# detcord-mdrv.net
KiCad netlist of a schematic drawn in EAGLE
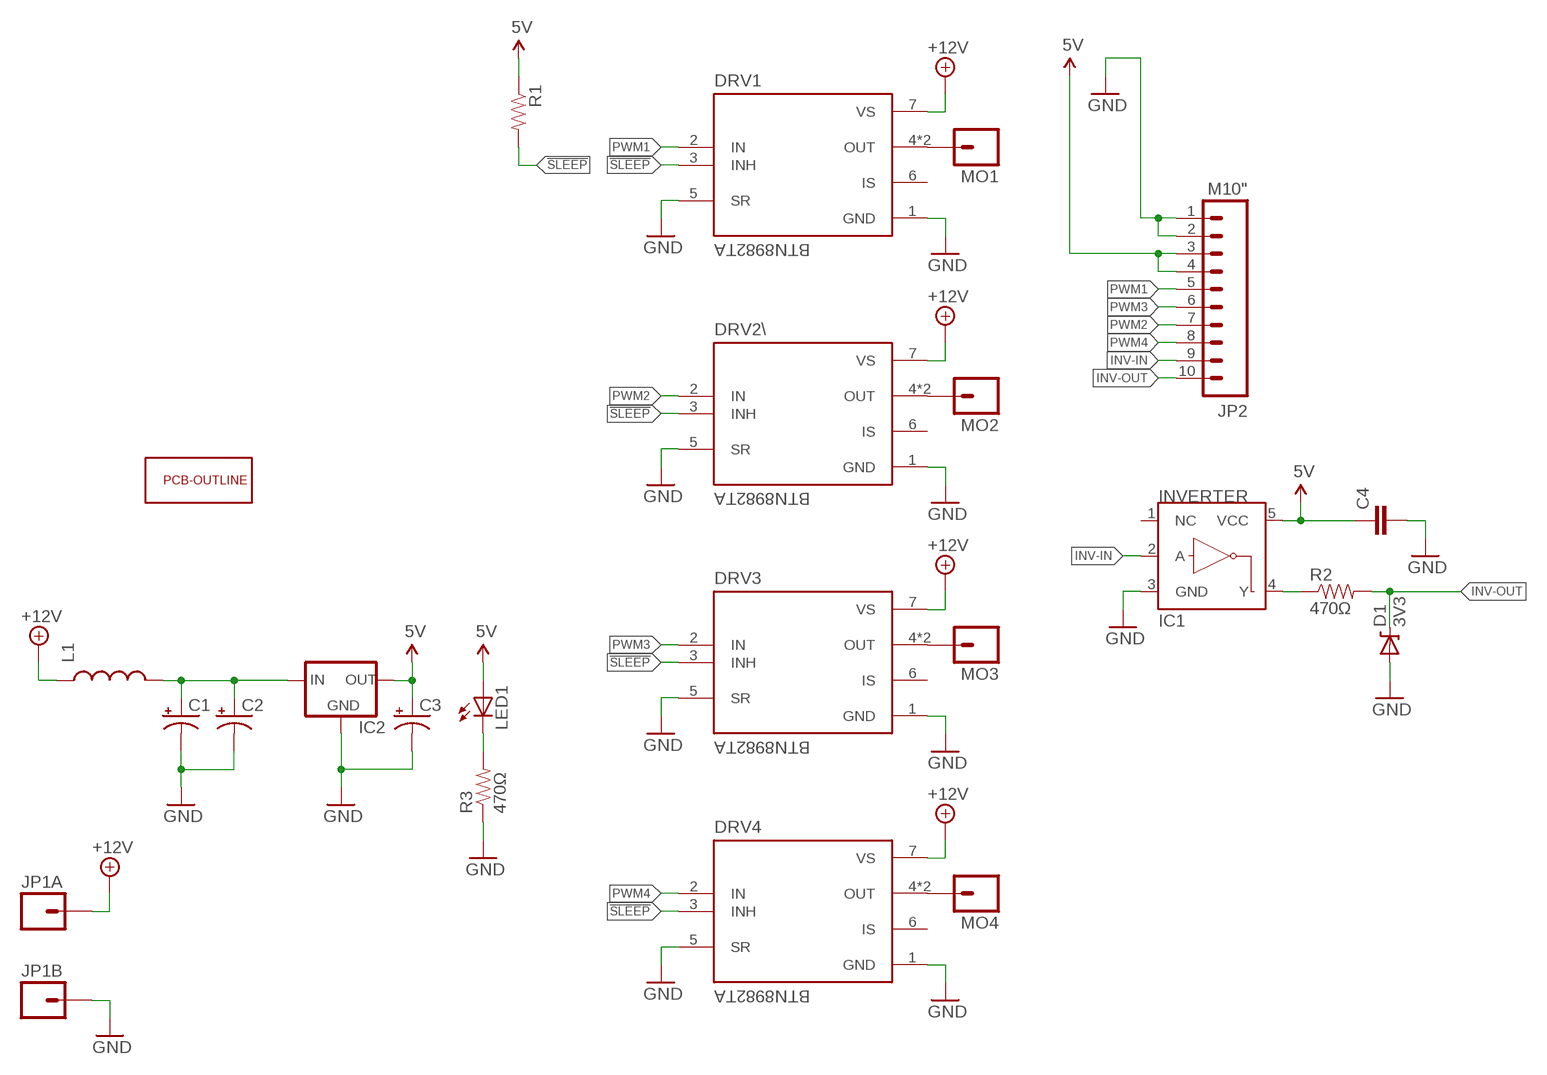
[diagram p0: schematic, sheet 1]

(export (version "E")
  (design (tool "Eeschema 10.0.6"))
  (components
    (comp (ref "C1")
      (value "CAP_POLD")
      (footprint "eagle-import:PANASONIC_D")
      (libsource (lib "eagle-import") (part "CAP_POLD"))
    )
    (comp (ref "C2")
      (value "CAP_POLD")
      (footprint "eagle-import:PANASONIC_D")
      (libsource (lib "eagle-import") (part "CAP_POLD"))
    )
    (comp (ref "C3")
      (value "CAP_POLD")
      (footprint "eagle-import:PANASONIC_D")
      (libsource (lib "eagle-import") (part "CAP_POLD"))
    )
    (comp (ref "C4")
      (value "CAP0603-CAP")
      (footprint "eagle-import:0603-CAP")
      (libsource (lib "eagle-import") (part "CAP0603-CAP"))
    )
    (comp (ref "D1")
      (value "3V3")
      (footprint "eagle-import:SOD-323")
      (libsource (lib "eagle-import") (part "DIODE-ZENER-BZT52"))
    )
    (comp (ref "DRV1")
      (value "BTN8982TA")
      (footprint "eagle-import:DPAK127P1500X440-8N")
      (fields (field (name "MF") "Infineon Technologies"))
      (libsource (lib "eagle-import") (part "BTN8982TA"))
    )
    (comp (ref "DRV2\\")
      (value "BTN8982TA")
      (footprint "eagle-import:DPAK127P1500X440-8N")
      (fields (field (name "MF") "Infineon Technologies"))
      (libsource (lib "eagle-import") (part "BTN8982TA"))
    )
    (comp (ref "DRV3")
      (value "BTN8982TA")
      (footprint "eagle-import:DPAK127P1500X440-8N")
      (fields (field (name "MF") "Infineon Technologies"))
      (libsource (lib "eagle-import") (part "BTN8982TA"))
    )
    (comp (ref "DRV4")
      (value "BTN8982TA")
      (footprint "eagle-import:DPAK127P1500X440-8N")
      (fields (field (name "MF") "Infineon Technologies"))
      (libsource (lib "eagle-import") (part "BTN8982TA"))
    )
    (comp (ref "IC1")
      (value "INVERTER")
      (footprint "eagle-import:SC70")
      (libsource (lib "eagle-import") (part "INVERTER{dblquote}{dblquote}"))
    )
    (comp (ref "IC2")
      (value "V_REG_78XXSINK")
      (footprint "eagle-import:TO220-IGO")
      (libsource (lib "eagle-import") (part "V_REG_78XXSINK"))
    )
    (comp (ref "JP1A")
      (value "M01PTH_2MM")
      (footprint "eagle-import:1X01_2MM")
      (libsource (lib "eagle-import") (part "M01PTH_2MM"))
    )
    (comp (ref "JP1B")
      (value "M01PTH_2MM")
      (footprint "eagle-import:1X01_2MM")
      (libsource (lib "eagle-import") (part "M01PTH_2MM"))
    )
    (comp (ref "JP2")
      (value "M10\"")
      (footprint "eagle-import:1X10")
      (libsource (lib "eagle-import") (part "M10{dblquote}"))
    )
    (comp (ref "L1")
      (value "INDUCTORCR54")
      (footprint "eagle-import:CR54")
      (libsource (lib "eagle-import") (part "INDUCTORCR54"))
    )
    (comp (ref "LED1")
      (value "LED0603")
      (footprint "eagle-import:LED-0603")
      (libsource (lib "eagle-import") (part "LED0603"))
    )
    (comp (ref "MO1")
      (value "M01PTH_2MM")
      (footprint "eagle-import:1X01_2MM")
      (libsource (lib "eagle-import") (part "M01PTH_2MM"))
    )
    (comp (ref "MO2")
      (value "M01PTH_2MM")
      (footprint "eagle-import:1X01_2MM")
      (libsource (lib "eagle-import") (part "M01PTH_2MM"))
    )
    (comp (ref "MO3")
      (value "M01PTH_2MM")
      (footprint "eagle-import:1X01_2MM")
      (libsource (lib "eagle-import") (part "M01PTH_2MM"))
    )
    (comp (ref "MO4")
      (value "M01PTH_2MM")
      (footprint "eagle-import:1X01_2MM")
      (libsource (lib "eagle-import") (part "M01PTH_2MM"))
    )
    (comp (ref "PCBOUTLINE1")
      (value "PCB-OUTLINE-38X24MM")
      (footprint "eagle-import:PCB-OUTLINE-38X24MM")
      (libsource (lib "eagle-import") (part "PCB-OUTLINE-38X24MM"))
    )
    (comp (ref "R1")
      (value "RESISTOR0603-RES")
      (footprint "eagle-import:0603-RES")
      (libsource (lib "eagle-import") (part "RESISTOR0603-RES"))
    )
    (comp (ref "R2")
      (value "470Ω")
      (footprint "eagle-import:0603-RES")
      (libsource (lib "eagle-import") (part "RESISTOR0603-RES"))
    )
    (comp (ref "R3")
      (value "470Ω")
      (footprint "eagle-import:0603-RES")
      (libsource (lib "eagle-import") (part "RESISTOR0603-RES"))
    )
  )
  (nets
    (net (code "1") (name "+12V") (class "Default")
      (node (ref "DRV1") (pin "7") (pinfunction "VS_7") (pintype "power_in"))
      (node (ref "DRV2\\") (pin "7") (pinfunction "VS_7") (pintype "power_in"))
      (node (ref "DRV3") (pin "7") (pinfunction "VS_7") (pintype "power_in"))
      (node (ref "DRV4") (pin "7") (pinfunction "VS_7") (pintype "power_in"))
      (node (ref "JP1A") (pin "1") (pinfunction "1_1") (pintype "passive"))
      (node (ref "L1") (pin "P$1") (pinfunction "1_P$1") (pintype "passive"))
    )
    (net (code "2") (name "/~{SLEEP}") (class "Default")
      (node (ref "DRV1") (pin "3") (pinfunction "INH_3") (pintype "input"))
      (node (ref "DRV2\\") (pin "3") (pinfunction "INH_3") (pintype "input"))
      (node (ref "DRV3") (pin "3") (pinfunction "INH_3") (pintype "input"))
      (node (ref "DRV4") (pin "3") (pinfunction "INH_3") (pintype "input"))
      (node (ref "R1") (pin "2") (pinfunction "2_2") (pintype "passive"))
    )
    (net (code "3") (name "5V") (class "Default")
      (node (ref "C3") (pin "+") (pinfunction "+_+") (pintype "passive"))
      (node (ref "C4") (pin "1") (pinfunction "1_1") (pintype "passive"))
      (node (ref "IC1") (pin "5") (pinfunction "VCC_5") (pintype "bidirectional"))
      (node (ref "IC2") (pin "OUT") (pinfunction "OUT_OUT") (pintype "output"))
      (node (ref "JP2") (pin "3") (pinfunction "3_3") (pintype "passive"))
      (node (ref "JP2") (pin "4") (pinfunction "4_4") (pintype "passive"))
      (node (ref "LED1") (pin "A") (pinfunction "A_A") (pintype "passive"))
      (node (ref "R1") (pin "1") (pinfunction "1_1") (pintype "passive"))
    )
    (net (code "4") (name "GND") (class "Default")
      (node (ref "C1") (pin "-") (pinfunction "-_-") (pintype "passive"))
      (node (ref "C2") (pin "-") (pinfunction "-_-") (pintype "passive"))
      (node (ref "C3") (pin "-") (pinfunction "-_-") (pintype "passive"))
      (node (ref "C4") (pin "2") (pinfunction "2_2") (pintype "passive"))
      (node (ref "D1") (pin "2") (pinfunction "A_2") (pintype "passive"))
      (node (ref "DRV1") (pin "1") (pinfunction "GND_1") (pintype "power_in"))
      (node (ref "DRV1") (pin "5") (pinfunction "SR_5") (pintype "input"))
      (node (ref "DRV2\\") (pin "1") (pinfunction "GND_1") (pintype "power_in"))
      (node (ref "DRV2\\") (pin "5") (pinfunction "SR_5") (pintype "input"))
      (node (ref "DRV3") (pin "1") (pinfunction "GND_1") (pintype "power_in"))
      (node (ref "DRV3") (pin "5") (pinfunction "SR_5") (pintype "input"))
      (node (ref "DRV4") (pin "1") (pinfunction "GND_1") (pintype "power_in"))
      (node (ref "DRV4") (pin "5") (pinfunction "SR_5") (pintype "input"))
      (node (ref "IC1") (pin "3") (pinfunction "GND_3") (pintype "bidirectional"))
      (node (ref "IC2") (pin "GND") (pinfunction "GND_GND") (pintype "input"))
      (node (ref "JP1B") (pin "1") (pinfunction "1_1") (pintype "passive"))
      (node (ref "JP2") (pin "1") (pinfunction "1_1") (pintype "passive"))
      (node (ref "JP2") (pin "2") (pinfunction "2_2") (pintype "passive"))
      (node (ref "R3") (pin "1") (pinfunction "1_1") (pintype "passive"))
    )
    (net (code "5") (name "INV-IN") (class "Default")
      (node (ref "IC1") (pin "2") (pinfunction "A_2") (pintype "bidirectional"))
      (node (ref "JP2") (pin "9") (pinfunction "9_9") (pintype "passive"))
    )
    (net (code "6") (name "INV-OUT") (class "Default")
      (node (ref "D1") (pin "1") (pinfunction "C_1") (pintype "passive"))
      (node (ref "JP2") (pin "10") (pinfunction "10_10") (pintype "passive"))
      (node (ref "R2") (pin "2") (pinfunction "2_2") (pintype "passive"))
    )
    (net (code "7") (name "Net-(DRV1-OUT-Pad4)") (class "Default")
      (node (ref "DRV1") (pin "4") (pinfunction "OUT_4") (pintype "output"))
      (node (ref "DRV1") (pin "8") (pinfunction "OUT_8") (pintype "output"))
      (node (ref "MO1") (pin "1") (pinfunction "1_1") (pintype "passive"))
    )
    (net (code "8") (name "Net-(DRV2\\-OUT-Pad4)") (class "Default")
      (node (ref "DRV2\\") (pin "4") (pinfunction "OUT_4") (pintype "output"))
      (node (ref "DRV2\\") (pin "8") (pinfunction "OUT_8") (pintype "output"))
      (node (ref "MO2") (pin "1") (pinfunction "1_1") (pintype "passive"))
    )
    (net (code "9") (name "Net-(DRV3-OUT-Pad4)") (class "Default")
      (node (ref "DRV3") (pin "4") (pinfunction "OUT_4") (pintype "output"))
      (node (ref "DRV3") (pin "8") (pinfunction "OUT_8") (pintype "output"))
      (node (ref "MO3") (pin "1") (pinfunction "1_1") (pintype "passive"))
    )
    (net (code "10") (name "Net-(DRV4-OUT-Pad4)") (class "Default")
      (node (ref "DRV4") (pin "4") (pinfunction "OUT_4") (pintype "output"))
      (node (ref "DRV4") (pin "8") (pinfunction "OUT_8") (pintype "output"))
      (node (ref "MO4") (pin "1") (pinfunction "1_1") (pintype "passive"))
    )
    (net (code "11") (name "Net-(IC1-Y)") (class "Default")
      (node (ref "IC1") (pin "4") (pinfunction "Y_4") (pintype "bidirectional"))
      (node (ref "R2") (pin "1") (pinfunction "1_1") (pintype "passive"))
    )
    (net (code "12") (name "Net-(L1-2)") (class "Default")
      (node (ref "C1") (pin "+") (pinfunction "+_+") (pintype "passive"))
      (node (ref "C2") (pin "+") (pinfunction "+_+") (pintype "passive"))
      (node (ref "IC2") (pin "IN") (pinfunction "IN_IN") (pintype "input"))
      (node (ref "L1") (pin "P$2") (pinfunction "2_P$2") (pintype "passive"))
    )
    (net (code "13") (name "Net-(LED1-PadC)") (class "Default")
      (node (ref "LED1") (pin "C") (pinfunction "C_C") (pintype "passive"))
      (node (ref "R3") (pin "2") (pinfunction "2_2") (pintype "passive"))
    )
    (net (code "14") (name "PWM1") (class "Default")
      (node (ref "DRV1") (pin "2") (pinfunction "IN_2") (pintype "input"))
      (node (ref "JP2") (pin "5") (pinfunction "5_5") (pintype "passive"))
    )
    (net (code "15") (name "PWM2") (class "Default")
      (node (ref "DRV2\\") (pin "2") (pinfunction "IN_2") (pintype "input"))
      (node (ref "JP2") (pin "7") (pinfunction "7_7") (pintype "passive"))
    )
    (net (code "16") (name "PWM3") (class "Default")
      (node (ref "DRV3") (pin "2") (pinfunction "IN_2") (pintype "input"))
      (node (ref "JP2") (pin "6") (pinfunction "6_6") (pintype "passive"))
    )
    (net (code "17") (name "PWM4") (class "Default")
      (node (ref "DRV4") (pin "2") (pinfunction "IN_2") (pintype "input"))
      (node (ref "JP2") (pin "8") (pinfunction "8_8") (pintype "passive"))
    )
    (net (code "18") (name "unconnected-(DRV1-IS-Pad6)") (class "Default")
      (node (ref "DRV1") (pin "6") (pinfunction "IS_6") (pintype "output"))
    )
    (net (code "19") (name "unconnected-(DRV2\\-IS-Pad6)") (class "Default")
      (node (ref "DRV2\\") (pin "6") (pinfunction "IS_6") (pintype "output"))
    )
    (net (code "20") (name "unconnected-(DRV3-IS-Pad6)") (class "Default")
      (node (ref "DRV3") (pin "6") (pinfunction "IS_6") (pintype "output"))
    )
    (net (code "21") (name "unconnected-(DRV4-IS-Pad6)") (class "Default")
      (node (ref "DRV4") (pin "6") (pinfunction "IS_6") (pintype "output"))
    )
    (net (code "22") (name "unconnected-(IC1-NC-Pad1)") (class "Default")
      (node (ref "IC1") (pin "1") (pinfunction "NC_1") (pintype "bidirectional"))
    )
  )
)
